# PSFB_transformer.net
KiCad netlist of a schematic drawn in Altium Designer
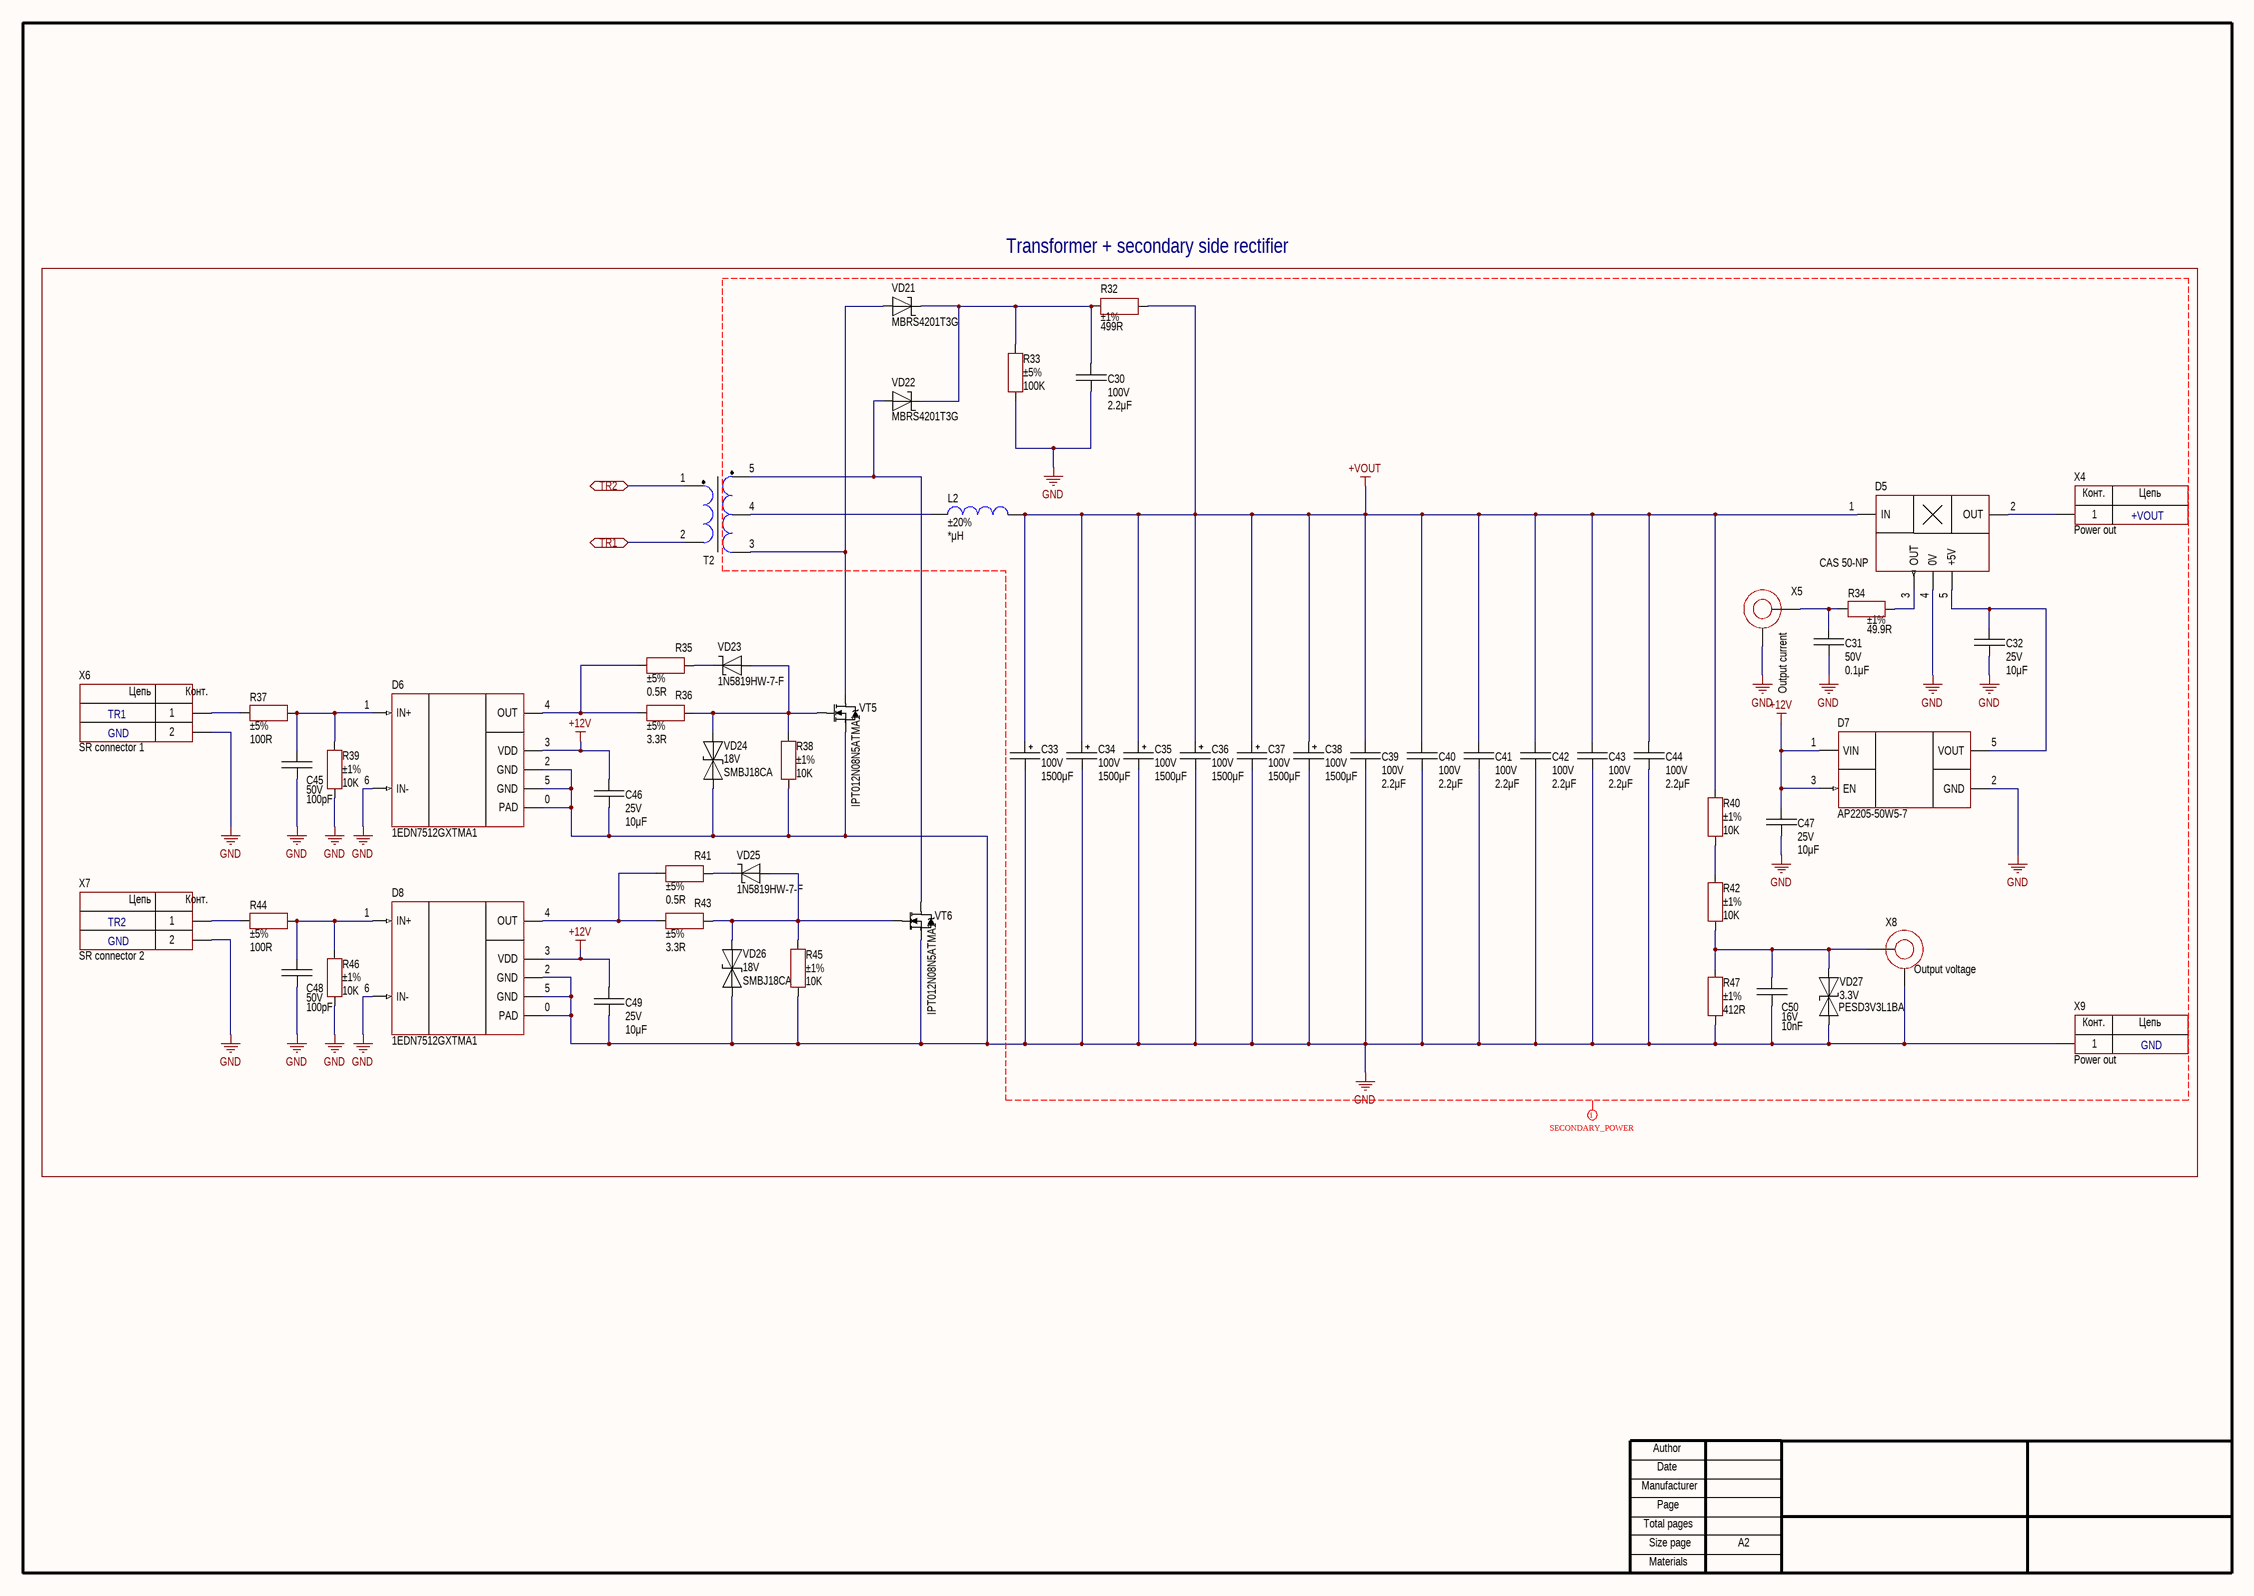
[diagram p0: PSFB_transformer.SchDoc]

(export (version "E")
  (design (tool "Eeschema 10.0.6"))
  (components
    (comp (ref "C30")
      (value "2.2μF")
      (footprint "CAP: 1206")
      (description "2.2µF ±10% 100V Ceramic Capacitor X7R 1206 (3216 Metric)")
      (fields
        (field (name "MANUFACTURER") "Yageo")
        (field (name "PARTNUMBER") "CC1206KKX7R0BB225")
        (field (name "VOLTAGE") "100V")
      )
      (libsource (lib "capacitor") (part "Ceramic_1206"))
    )
    (comp (ref "C31")
      (value "0.1μF")
      (footprint "CAP: 0805")
      (description "0.1µF ±10% 50V Ceramic Capacitor X7R 0805 (2012 Metric)")
      (fields
        (field (name "MANUFACTURER") "Yageo")
        (field (name "PARTNUMBER") "CC0805KRX7R9BB104")
        (field (name "VOLTAGE") "50V")
      )
      (libsource (lib "capacitor") (part "Ceramic_0805"))
    )
    (comp (ref "C32")
      (value "10μF")
      (footprint "CAP: 1206")
      (description "10µF ±10% 25V Ceramic Capacitor X7R 1206 (3216 Metric)")
      (fields
        (field (name "MANUFACTURER") "Yageo")
        (field (name "PARTNUMBER") "CC1206KKX7R8BB106")
        (field (name "VOLTAGE") "25V")
      )
      (libsource (lib "capacitor") (part "Ceramic_1206"))
    )
    (comp (ref "C33")
      (value "1500μF")
      (footprint "CAP: D30C10H37")
      (description "1500µF 100V Aluminum Electrolytic Capacitors Radial, Can - Snap-In  5000 Hrs @ 105°C")
      (fields
        (field (name "MANUFACTURER") "Nichicon")
        (field (name "PARTNUMBER") "LGY2A152MELB30")
        (field (name "VOLTAGE") "100V")
      )
      (libsource (lib "capacitor") (part "Aluminium"))
    )
    (comp (ref "C34")
      (value "1500μF")
      (footprint "CAP: D30C10H37")
      (description "1500µF 100V Aluminum Electrolytic Capacitors Radial, Can - Snap-In  5000 Hrs @ 105°C")
      (fields
        (field (name "MANUFACTURER") "Nichicon")
        (field (name "PARTNUMBER") "LGY2A152MELB30")
        (field (name "VOLTAGE") "100V")
      )
      (libsource (lib "capacitor") (part "Aluminium"))
    )
    (comp (ref "C35")
      (value "1500μF")
      (footprint "CAP: D30C10H37")
      (description "1500µF 100V Aluminum Electrolytic Capacitors Radial, Can - Snap-In  5000 Hrs @ 105°C")
      (fields
        (field (name "MANUFACTURER") "Nichicon")
        (field (name "PARTNUMBER") "LGY2A152MELB30")
        (field (name "VOLTAGE") "100V")
      )
      (libsource (lib "capacitor") (part "Aluminium"))
    )
    (comp (ref "C36")
      (value "1500μF")
      (footprint "CAP: D30C10H37")
      (description "1500µF 100V Aluminum Electrolytic Capacitors Radial, Can - Snap-In  5000 Hrs @ 105°C")
      (fields
        (field (name "MANUFACTURER") "Nichicon")
        (field (name "PARTNUMBER") "LGY2A152MELB30")
        (field (name "VOLTAGE") "100V")
      )
      (libsource (lib "capacitor") (part "Aluminium"))
    )
    (comp (ref "C37")
      (value "1500μF")
      (footprint "CAP: D30C10H37")
      (description "1500µF 100V Aluminum Electrolytic Capacitors Radial, Can - Snap-In  5000 Hrs @ 105°C")
      (fields
        (field (name "MANUFACTURER") "Nichicon")
        (field (name "PARTNUMBER") "LGY2A152MELB30")
        (field (name "VOLTAGE") "100V")
      )
      (libsource (lib "capacitor") (part "Aluminium"))
    )
    (comp (ref "C38")
      (value "1500μF")
      (footprint "CAP: D30C10H37")
      (description "1500µF 100V Aluminum Electrolytic Capacitors Radial, Can - Snap-In  5000 Hrs @ 105°C")
      (fields
        (field (name "MANUFACTURER") "Nichicon")
        (field (name "PARTNUMBER") "LGY2A152MELB30")
        (field (name "VOLTAGE") "100V")
      )
      (libsource (lib "capacitor") (part "Aluminium"))
    )
    (comp (ref "C39")
      (value "2.2μF")
      (footprint "CAP: 1206")
      (description "2.2µF ±10% 100V Ceramic Capacitor X7R 1206 (3216 Metric)")
      (fields
        (field (name "MANUFACTURER") "Yageo")
        (field (name "PARTNUMBER") "CC1206KKX7R0BB225")
        (field (name "VOLTAGE") "100V")
      )
      (libsource (lib "capacitor") (part "Ceramic_1206"))
    )
    (comp (ref "C40")
      (value "2.2μF")
      (footprint "CAP: 1206")
      (description "2.2µF ±10% 100V Ceramic Capacitor X7R 1206 (3216 Metric)")
      (fields
        (field (name "MANUFACTURER") "Yageo")
        (field (name "PARTNUMBER") "CC1206KKX7R0BB225")
        (field (name "VOLTAGE") "100V")
      )
      (libsource (lib "capacitor") (part "Ceramic_1206"))
    )
    (comp (ref "C41")
      (value "2.2μF")
      (footprint "CAP: 1206")
      (description "2.2µF ±10% 100V Ceramic Capacitor X7R 1206 (3216 Metric)")
      (fields
        (field (name "MANUFACTURER") "Yageo")
        (field (name "PARTNUMBER") "CC1206KKX7R0BB225")
        (field (name "VOLTAGE") "100V")
      )
      (libsource (lib "capacitor") (part "Ceramic_1206"))
    )
    (comp (ref "C42")
      (value "2.2μF")
      (footprint "CAP: 1206")
      (description "2.2µF ±10% 100V Ceramic Capacitor X7R 1206 (3216 Metric)")
      (fields
        (field (name "MANUFACTURER") "Yageo")
        (field (name "PARTNUMBER") "CC1206KKX7R0BB225")
        (field (name "VOLTAGE") "100V")
      )
      (libsource (lib "capacitor") (part "Ceramic_1206"))
    )
    (comp (ref "C43")
      (value "2.2μF")
      (footprint "CAP: 1206")
      (description "2.2µF ±10% 100V Ceramic Capacitor X7R 1206 (3216 Metric)")
      (fields
        (field (name "MANUFACTURER") "Yageo")
        (field (name "PARTNUMBER") "CC1206KKX7R0BB225")
        (field (name "VOLTAGE") "100V")
      )
      (libsource (lib "capacitor") (part "Ceramic_1206"))
    )
    (comp (ref "C44")
      (value "2.2μF")
      (footprint "CAP: 1206")
      (description "2.2µF ±10% 100V Ceramic Capacitor X7R 1206 (3216 Metric)")
      (fields
        (field (name "MANUFACTURER") "Yageo")
        (field (name "PARTNUMBER") "CC1206KKX7R0BB225")
        (field (name "VOLTAGE") "100V")
      )
      (libsource (lib "capacitor") (part "Ceramic_1206"))
    )
    (comp (ref "C45")
      (value "100pF")
      (footprint "CAP: 0805")
      (description "100pF ±5% 50V Ceramic Capacitor C0G, NP0 0805 (2012 Metric)")
      (fields
        (field (name "MANUFACTURER") "Yageo")
        (field (name "PARTNUMBER") "CC0805JRNPO9BN101")
        (field (name "VOLTAGE") "50V")
      )
      (libsource (lib "capacitor") (part "Ceramic_0805"))
    )
    (comp (ref "C46")
      (value "10μF")
      (footprint "CAP: 1206")
      (description "10µF ±10% 25V Ceramic Capacitor X7R 1206 (3216 Metric)")
      (fields
        (field (name "MANUFACTURER") "Yageo")
        (field (name "PARTNUMBER") "CC1206KKX7R8BB106")
        (field (name "VOLTAGE") "25V")
      )
      (libsource (lib "capacitor") (part "Ceramic_1206"))
    )
    (comp (ref "C47")
      (value "10μF")
      (footprint "CAP: 1206")
      (description "10µF ±10% 25V Ceramic Capacitor X7R 1206 (3216 Metric)")
      (fields
        (field (name "MANUFACTURER") "Yageo")
        (field (name "PARTNUMBER") "CC1206KKX7R8BB106")
        (field (name "VOLTAGE") "25V")
      )
      (libsource (lib "capacitor") (part "Ceramic_1206"))
    )
    (comp (ref "C48")
      (value "100pF")
      (footprint "CAP: 0805")
      (description "100pF ±5% 50V Ceramic Capacitor C0G, NP0 0805 (2012 Metric)")
      (fields
        (field (name "MANUFACTURER") "Yageo")
        (field (name "PARTNUMBER") "CC0805JRNPO9BN101")
        (field (name "VOLTAGE") "50V")
      )
      (libsource (lib "capacitor") (part "Ceramic_0805"))
    )
    (comp (ref "C49")
      (value "10μF")
      (footprint "CAP: 1206")
      (description "10µF ±10% 25V Ceramic Capacitor X7R 1206 (3216 Metric)")
      (fields
        (field (name "MANUFACTURER") "Yageo")
        (field (name "PARTNUMBER") "CC1206KKX7R8BB106")
        (field (name "VOLTAGE") "25V")
      )
      (libsource (lib "capacitor") (part "Ceramic_1206"))
    )
    (comp (ref "C50")
      (value "10nF")
      (footprint "CAP: 0805")
      (description "27pF ±5% 50V Ceramic Capacitor C0G, NP0 0805 (2012 Metric)")
      (fields
        (field (name "MANUFACTURER") "Yageo")
        (field (name "PARTNUMBER") "CC0805JKNPO7BN103")
        (field (name "VOLTAGE") "16V")
      )
      (libsource (lib "capacitor") (part "Ceramic_0805"))
    )
    (comp (ref "D5")
      (value "~")
      (footprint "SENSOR: LTS 25-NP")
      (description "Current Sensor 50A 1 Channel Flux Gate, Closed Loop Bidirectional Module")
      (fields
        (field (name "MANUFACTURER") "LEM")
        (field (name "VALUEMANUFACTURERPARTNUMBER") "IC current sensors, 50A, ±0.2%, 400 kHz, 12.5mV/A, -40...+85°C")
        (field (name "PARTNUMBER") "CAS 50-NP")
      )
      (libsource (lib "ic-sensor") (part "LTS 25-NP"))
    )
    (comp (ref "D6")
      (value "~")
      (footprint "6-WDFN")
      (description "Low-Side Gate Driver IC Inverting, Non-Inverting PG-WSON-6-1")
      (fields
        (field (name "MANUFACTURER") "Infineon")
        (field (name "VALUEMANUFACTURERPARTNUMBER") "Low gate driver, Non-Inverting, complementary, +4/-8A, 6.5/4.5ns, 4.5...20V, -55...+150°C, 6-WDFN")
        (field (name "PARTNUMBER") "1EDN7512GXTMA1")
      )
      (libsource (lib "MyLib") (part "1EDN7512BXTSA1"))
    )
    (comp (ref "D7")
      (value "~")
      (footprint "SOT23-5")
      (description "Linear Voltage Regulator IC Positive Fixed 1 Output  250mA SOT-25")
      (fields
        (field (name "MANUFACTURER") "Diodes Incorporated")
        (field (name "VALUEMANUFACTURERPARTNUMBER") "Linear voltage regulator, input 4...24V, 0.5V, output 5.0V, 0.25A, -40...+85°C, SOT23-6")
        (field (name "PARTNUMBER") "AP2205-50W5-7")
      )
      (libsource (lib "ic-power-supply") (part "AP2204K-3.3TRG1"))
    )
    (comp (ref "D8")
      (value "~")
      (footprint "6-WDFN")
      (description "Low-Side Gate Driver IC Inverting, Non-Inverting PG-WSON-6-1")
      (fields
        (field (name "MANUFACTURER") "Infineon")
        (field (name "VALUEMANUFACTURERPARTNUMBER") "Low gate driver, Non-Inverting, complementary, +4/-8A, 6.5/4.5ns, 4.5...20V, -55...+150°C, 6-WDFN")
        (field (name "PARTNUMBER") "1EDN7512GXTMA1")
      )
      (libsource (lib "MyLib") (part "1EDN7512BXTSA1"))
    )
    (comp (ref "L2")
      (value "*μH")
      (footprint "IND: R46.7/24.1/18 (H)")
      (description "Custom inductor, DNP")
      (fields
        (field (name "MANUFACTURER") "Magnetics")
        (field (name "PARTNUMBER") "0077438A7")
        (field (name "TOLERANCE") "±20%")
      )
      (libsource (lib "inductor") (part "Inductor_R46.7/24.1/18"))
    )
    (comp (ref "R32")
      (value "499R")
      (footprint "RES: 2512")
      (description "499 Ohms ±1% 1W Chip Resistor 2512 (6432 Metric) Moisture Resistant Thick Film")
      (fields
        (field (name "MANUFACTURER") "Yageo")
        (field (name "PARTNUMBER") "RC2512FK-07499RL")
        (field (name "TOLERANCE") "±1%")
      )
      (libsource (lib "resistor") (part "Resistor_2512"))
    )
    (comp (ref "R33")
      (value "100K")
      (footprint "RES: 1206")
      (description "100 kOhms ±5% 0.25W, 1/4W Chip Resistor 1206 (3216 Metric) Moisture Resistant Thick Film")
      (fields
        (field (name "MANUFACTURER") "Yageo")
        (field (name "PARTNUMBER") "RC1206JR-07100KL")
        (field (name "TOLERANCE") "±5%")
      )
      (libsource (lib "") (part "Resistor_1206_1"))
    )
    (comp (ref "R34")
      (value "49.9R")
      (footprint "RES: 0805")
      (description "49.9 Ohms ±1% 0.125W, 1/8W Chip Resistor 0805 (2012 Metric) Moisture Resistant Thick Film")
      (fields
        (field (name "MANUFACTURER") "Yageo")
        (field (name "PARTNUMBER") "RC0805FR-0749R9L")
        (field (name "TOLERANCE") "±1%")
      )
      (libsource (lib "") (part "Resistor_0805_1"))
    )
    (comp (ref "R35")
      (value "0.5R")
      (footprint "RES: 1206")
      (fields
        (field (name "MANUFACTURER") "Yageo")
        (field (name "PARTNUMBER") "RL1206JR-070R5L")
        (field (name "VALUEMANUFACTURERPARTNUMBER") "Resistor film, 0.5R, ±5%, 1206, 0.25W, -55...+125°C")
        (field (name "TOLERANCE") "±5%")
      )
      (libsource (lib "resistor") (part "Resistor_1206"))
    )
    (comp (ref "R36")
      (value "3.3R")
      (footprint "RES: 1206")
      (description "3.3 Ohms ±5% 0.25W, 1/4W Chip Resistor 1206 (3216 Metric) Moisture Resistant Thick Film")
      (fields
        (field (name "MANUFACTURER") "Yageo")
        (field (name "PARTNUMBER") "RC1206JR-073R3L")
        (field (name "TOLERANCE") "±5%")
      )
      (libsource (lib "resistor") (part "Resistor_1206"))
    )
    (comp (ref "R37")
      (value "100R")
      (footprint "RES: 0805")
      (description "100 Ohms ±5% 0.125W, 1/8W Chip Resistor 0805 (2012 Metric) Moisture Resistant Thick Film")
      (fields
        (field (name "MANUFACTURER") "Yageo")
        (field (name "PARTNUMBER") "RC0805JR-07100RL")
        (field (name "TOLERANCE") "±5%")
      )
      (libsource (lib "resistor") (part "Resistor_0805"))
    )
    (comp (ref "R38")
      (value "10K")
      (footprint "RES: 0805")
      (description "10 kOhms ±1% 0.125W, 1/8W Chip Resistor 0805 (2012 Metric) Moisture Resistant Thick Film")
      (fields
        (field (name "MANUFACTURER") "Yageo")
        (field (name "PARTNUMBER") "RC0805FR-0710KL")
        (field (name "TOLERANCE") "±1%")
      )
      (libsource (lib "resistor") (part "Resistor_0805"))
    )
    (comp (ref "R39")
      (value "10K")
      (footprint "RES: 0805")
      (description "10 kOhms ±1% 0.125W, 1/8W Chip Resistor 0805 (2012 Metric) Moisture Resistant Thick Film")
      (fields
        (field (name "MANUFACTURER") "Yageo")
        (field (name "PARTNUMBER") "RC0805FR-0710KL")
        (field (name "TOLERANCE") "±1%")
      )
      (libsource (lib "resistor") (part "Resistor_0805"))
    )
    (comp (ref "R40")
      (value "10K")
      (footprint "RES: 0805")
      (description "10 kOhms ±1% 0.125W, 1/8W Chip Resistor 0805 (2012 Metric) Moisture Resistant Thick Film")
      (fields
        (field (name "MANUFACTURER") "Yageo")
        (field (name "PARTNUMBER") "RC0805FR-0710KL")
        (field (name "TOLERANCE") "±1%")
      )
      (libsource (lib "resistor") (part "Resistor_0805"))
    )
    (comp (ref "R41")
      (value "0.5R")
      (footprint "RES: 1206")
      (fields
        (field (name "MANUFACTURER") "Yageo")
        (field (name "PARTNUMBER") "RL1206JR-070R5L")
        (field (name "VALUEMANUFACTURERPARTNUMBER") "Resistor film, 0.5R, ±5%, 1206, 0.25W, -55...+125°C")
        (field (name "TOLERANCE") "±5%")
      )
      (libsource (lib "resistor") (part "Resistor_1206"))
    )
    (comp (ref "R42")
      (value "10K")
      (footprint "RES: 0805")
      (description "10 kOhms ±1% 0.125W, 1/8W Chip Resistor 0805 (2012 Metric) Moisture Resistant Thick Film")
      (fields
        (field (name "MANUFACTURER") "Yageo")
        (field (name "PARTNUMBER") "RC0805FR-0710KL")
        (field (name "TOLERANCE") "±1%")
      )
      (libsource (lib "resistor") (part "Resistor_0805"))
    )
    (comp (ref "R43")
      (value "3.3R")
      (footprint "RES: 1206")
      (description "3.3 Ohms ±5% 0.25W, 1/4W Chip Resistor 1206 (3216 Metric) Moisture Resistant Thick Film")
      (fields
        (field (name "MANUFACTURER") "Yageo")
        (field (name "PARTNUMBER") "RC1206JR-073R3L")
        (field (name "TOLERANCE") "±5%")
      )
      (libsource (lib "resistor") (part "Resistor_1206"))
    )
    (comp (ref "R44")
      (value "100R")
      (footprint "RES: 0805")
      (description "100 Ohms ±5% 0.125W, 1/8W Chip Resistor 0805 (2012 Metric) Moisture Resistant Thick Film")
      (fields
        (field (name "MANUFACTURER") "Yageo")
        (field (name "PARTNUMBER") "RC0805JR-07100RL")
        (field (name "TOLERANCE") "±5%")
      )
      (libsource (lib "resistor") (part "Resistor_0805"))
    )
    (comp (ref "R45")
      (value "10K")
      (footprint "RES: 0805")
      (description "10 kOhms ±1% 0.125W, 1/8W Chip Resistor 0805 (2012 Metric) Moisture Resistant Thick Film")
      (fields
        (field (name "MANUFACTURER") "Yageo")
        (field (name "PARTNUMBER") "RC0805FR-0710KL")
        (field (name "TOLERANCE") "±1%")
      )
      (libsource (lib "resistor") (part "Resistor_0805"))
    )
    (comp (ref "R46")
      (value "10K")
      (footprint "RES: 0805")
      (description "10 kOhms ±1% 0.125W, 1/8W Chip Resistor 0805 (2012 Metric) Moisture Resistant Thick Film")
      (fields
        (field (name "MANUFACTURER") "Yageo")
        (field (name "PARTNUMBER") "RC0805FR-0710KL")
        (field (name "TOLERANCE") "±1%")
      )
      (libsource (lib "resistor") (part "Resistor_0805"))
    )
    (comp (ref "R47")
      (value "412R")
      (footprint "RES: 0805")
      (description "412 Ohms ±1% 0.125W, 1/8W Chip Resistor 0805 (2012 Metric) Moisture Resistant Thick Film")
      (fields
        (field (name "MANUFACTURER") "Yageo")
        (field (name "PARTNUMBER") "RC0805FR-07412RL")
        (field (name "TOLERANCE") "±1%")
      )
      (libsource (lib "resistor") (part "Resistor_0805"))
    )
    (comp (ref "T2")
      (value "~")
      (footprint "TRANS: ETD59/31/22_FB")
      (description "N97 B66397G0000X197 сore / B66398W1024T001 coil former")
      (fields
        (field (name "MANUFACTURER") "Epcos")
        (field (name "VALUEMANUFACTURERPARTNUMBER") "Transformer, ")
      )
      (libsource (lib "transformer") (part "ETD59/31/22_FB"))
    )
    (comp (ref "VD21")
      (value "~")
      (footprint "DIODE: SMC")
      (description "Diode Schottky 200V 4A Surface Mount SMC")
      (fields
        (field (name "MANUFACTURER") "Diodes Incorporated")
        (field (name "VALUEMANUFACTURERPARTNUMBER") "Schottky diode, 200V, 1A, 0.45V, 20pF, SMC, -55...+150°C")
        (field (name "PARTNUMBER") "MBRS4201T3G")
      )
      (libsource (lib "diode") (part "Schottky_single"))
    )
    (comp (ref "VD22")
      (value "~")
      (footprint "DIODE: SMC")
      (description "Diode Schottky 200V 4A Surface Mount SMC")
      (fields
        (field (name "MANUFACTURER") "Diodes Incorporated")
        (field (name "VALUEMANUFACTURERPARTNUMBER") "Schottky diode, 200V, 1A, 0.45V, 20pF, SMC, -55...+150°C")
        (field (name "PARTNUMBER") "MBRS4201T3G")
      )
      (libsource (lib "diode") (part "Schottky_single"))
    )
    (comp (ref "VD23")
      (value "~")
      (footprint "DIODE: SOD123")
      (description "Diode Schottky 40V 1A Surface Mount SOD-123C")
      (fields
        (field (name "MANUFACTURER") "Diodes Incorporated")
        (field (name "VALUEMANUFACTURERPARTNUMBER") "Schottky diode, 40V, 1A, 0.45V, 15pF, SOD-123, -55...+150°C")
        (field (name "PARTNUMBER") "1N5819HW-7-F")
      )
      (libsource (lib "diode") (part "Schottky_single"))
    )
    (comp (ref "VD24")
      (value "~")
      (footprint "DIODE: SMB")
      (description "29.2V Clamp 20.6A Ipp Tvs Diode Surface Mount DO-214AA (SMBJ)")
      (fields
        (field (name "MANUFACTURER") "Diodes Incorporated")
        (field (name "VALUEMANUFACTURERPARTNUMBER") "TVS diode, 18V, 600W, , , SMB, -55...+150°C")
        (field (name "VOLTAGE") "18V")
        (field (name "PARTNUMBER") "SMBJ18CA")
      )
      (libsource (lib "diode") (part "TVS_single"))
    )
    (comp (ref "VD25")
      (value "~")
      (footprint "DIODE: SOD123")
      (description "Diode Schottky 40V 1A Surface Mount SOD-123C")
      (fields
        (field (name "MANUFACTURER") "Diodes Incorporated")
        (field (name "VALUEMANUFACTURERPARTNUMBER") "Schottky diode, 40V, 1A, 0.45V, 15pF, SOD-123, -55...+150°C")
        (field (name "PARTNUMBER") "1N5819HW-7-F")
      )
      (libsource (lib "diode") (part "Schottky_single"))
    )
    (comp (ref "VD26")
      (value "~")
      (footprint "DIODE: SMB")
      (description "29.2V Clamp 20.6A Ipp Tvs Diode Surface Mount DO-214AA (SMBJ)")
      (fields
        (field (name "MANUFACTURER") "Diodes Incorporated")
        (field (name "VALUEMANUFACTURERPARTNUMBER") "TVS diode, 18V, 600W, , , SMB, -55...+150°C")
        (field (name "VOLTAGE") "18V")
        (field (name "PARTNUMBER") "SMBJ18CA")
      )
      (libsource (lib "diode") (part "TVS_single"))
    )
    (comp (ref "VD27")
      (value "~")
      (footprint "DIODE: SOD323")
      (description "3.3V Reverse Standoff 26V Clamp 18A (8/20µs) Ipp Tvs Diode Surface Mount SOD-323")
      (fields
        (field (name "MANUFACTURER") "Diodes Incorporated")
        (field (name "VALUEMANUFACTURERPARTNUMBER") "TVS diode, 3.3V, 500W, , , SOD-323, -55...+150°C")
        (field (name "VOLTAGE") "3.3V")
        (field (name "PARTNUMBER") "PESD3V3L1BA")
      )
      (libsource (lib "diode") (part "TVS_single"))
    )
    (comp (ref "VT5")
      (value "~")
      (footprint "8-TDSON")
      (description "N-Channel 80V 300A (Tc) 375W (Tc) Surface Mount PG-HSOF-8-1")
      (fields
        (field (name "MANUFACTURER") "Infineon Technologies")
        (field (name "VALUEMANUFACTURERPARTNUMBER") "MOSFET N-channel transistor, 100V, 300A, 223nC, 375W, 1.2mOhm, 17000pF, 8-TDSON, -55...+150°C")
        (field (name "PARTNUMBER") "IPT012N08N5ATMA1")
      )
      (libsource (lib "transistor") (part "MOSFET_N_123"))
    )
    (comp (ref "VT6")
      (value "~")
      (footprint "8-TDSON")
      (description "N-Channel 80V 300A (Tc) 375W (Tc) Surface Mount PG-HSOF-8-1")
      (fields
        (field (name "MANUFACTURER") "Infineon Technologies")
        (field (name "VALUEMANUFACTURERPARTNUMBER") "MOSFET N-channel transistor, 100V, 300A, 223nC, 375W, 1.2mOhm, 17000pF, 8-TDSON, -55...+150°C")
        (field (name "PARTNUMBER") "IPT012N08N5ATMA1")
      )
      (libsource (lib "transistor") (part "MOSFET_N_123"))
    )
    (comp (ref "X4")
      (value "~")
      (footprint "7461098_for HAL")
      (description "25 Pin Shank Terminal M6 Through Hole")
      (fields
        (field (name "MANUFACTURER") "Würth Elektronik")
        (field (name "VALUEMANUFACTURERPARTNUMBER") "Power connector, , 250A")
        (field (name "COMMENTTEXT") "Power out")
      )
      (libsource (lib "connector") (part "Connector_single_power"))
    )
    (comp (ref "X5")
      (value "~")
      (footprint "60311002111526")
      (description "SMA Connector Jack, Female Socket 50Ohm Through Hole Solder")
      (fields
        (field (name "MANUFACTURER") "Würth Elektronik")
        (field (name "VALUEMANUFACTURERPARTNUMBER") "Connector SMA, 50 Ohm, 6Hz")
        (field (name "COMMENTTEXT") "Output current")
      )
      (libsource (lib "connector") (part "Connector_SMA"))
    )
    (comp (ref "X6")
      (value "~")
      (footprint "SM02B-SRSS-TB(LF)(SN)")
      (description "Connector Header Surface Mount, Right Angle 2 position 0.039\" (1.00mm)")
      (fields
        (field (name "MANUFACTURER") "JST")
        (field (name "VALUEMANUFACTURERPARTNUMBER") "Connector, 2pin, 1.00mm, 50V, 25A")
        (field (name "COMMENTTEXT") "SR connector 1")
      )
      (libsource (lib "MyLib") (part "Connector_SM02B-SRSS"))
    )
    (comp (ref "X7")
      (value "~")
      (footprint "SM02B-SRSS-TB(LF)(SN)")
      (description "Connector Header Surface Mount, Right Angle 2 position 0.039\" (1.00mm)")
      (fields
        (field (name "MANUFACTURER") "JST")
        (field (name "VALUEMANUFACTURERPARTNUMBER") "Connector, 2pin, 1.00mm, 50V, 25A")
        (field (name "COMMENTTEXT") "SR connector 2")
      )
      (libsource (lib "MyLib") (part "Connector_SM02B-SRSS"))
    )
    (comp (ref "X8")
      (value "~")
      (footprint "60311002111526")
      (description "SMA Connector Jack, Female Socket 50Ohm Through Hole Solder")
      (fields
        (field (name "MANUFACTURER") "Würth Elektronik")
        (field (name "VALUEMANUFACTURERPARTNUMBER") "Connector SMA, 50 Ohm, 6Hz")
        (field (name "COMMENTTEXT") "Output voltage")
      )
      (libsource (lib "connector") (part "Connector_SMA"))
    )
    (comp (ref "X9")
      (value "~")
      (footprint "7461098_for HAL")
      (description "25 Pin Shank Terminal M6 Through Hole")
      (fields
        (field (name "MANUFACTURER") "Würth Elektronik")
        (field (name "VALUEMANUFACTURERPARTNUMBER") "Power connector, , 250A")
        (field (name "COMMENTTEXT") "Power out")
      )
      (libsource (lib "connector") (part "Connector_single_power"))
    )
  )
  (nets
    (net (code "1") (name "+12V") (class "Default")
      (node (ref "C46") (pin "1") (pinfunction "1_1") (pintype "passive"))
      (node (ref "C47") (pin "1") (pinfunction "1_1") (pintype "passive"))
      (node (ref "C49") (pin "1") (pinfunction "1_1") (pintype "passive"))
      (node (ref "D6") (pin "3") (pinfunction "VDD_3") (pintype "passive"))
      (node (ref "D7") (pin "1") (pinfunction "VIN_1") (pintype "passive"))
      (node (ref "D7") (pin "3") (pinfunction "EN_3") (pintype "input"))
      (node (ref "D8") (pin "3") (pinfunction "VDD_3") (pintype "passive"))
    )
    (net (code "2") (name "+VOUT") (class "Default")
      (node (ref "C33") (pin "1") (pinfunction "1_1") (pintype "passive"))
      (node (ref "C34") (pin "1") (pinfunction "1_1") (pintype "passive"))
      (node (ref "C35") (pin "1") (pinfunction "1_1") (pintype "passive"))
      (node (ref "C36") (pin "1") (pinfunction "1_1") (pintype "passive"))
      (node (ref "C37") (pin "1") (pinfunction "1_1") (pintype "passive"))
      (node (ref "C38") (pin "1") (pinfunction "1_1") (pintype "passive"))
      (node (ref "C39") (pin "1") (pinfunction "1_1") (pintype "passive"))
      (node (ref "C40") (pin "1") (pinfunction "1_1") (pintype "passive"))
      (node (ref "C41") (pin "1") (pinfunction "1_1") (pintype "passive"))
      (node (ref "C42") (pin "1") (pinfunction "1_1") (pintype "passive"))
      (node (ref "C43") (pin "1") (pinfunction "1_1") (pintype "passive"))
      (node (ref "C44") (pin "1") (pinfunction "1_1") (pintype "passive"))
      (node (ref "D5") (pin "1") (pinfunction "IN_1") (pintype "passive"))
      (node (ref "L2") (pin "1") (pinfunction "1_1") (pintype "passive"))
      (node (ref "R32") (pin "2") (pinfunction "2_2") (pintype "passive"))
      (node (ref "R40") (pin "2") (pinfunction "2_2") (pintype "passive"))
    )
    (net (code "3") (name "/TR1") (class "Default")
      (node (ref "T2") (pin "2") (pinfunction "2_2") (pintype "power_in"))
    )
    (net (code "4") (name "/TR2") (class "Default")
      (node (ref "T2") (pin "1") (pinfunction "1_1") (pintype "power_in"))
    )
    (net (code "5") (name "GND") (class "Default")
      (node (ref "C30") (pin "2") (pinfunction "2_2") (pintype "passive"))
      (node (ref "C31") (pin "1") (pinfunction "1_1") (pintype "passive"))
      (node (ref "C32") (pin "2") (pinfunction "2_2") (pintype "passive"))
      (node (ref "C33") (pin "2") (pinfunction "2_2") (pintype "passive"))
      (node (ref "C34") (pin "2") (pinfunction "2_2") (pintype "passive"))
      (node (ref "C35") (pin "2") (pinfunction "2_2") (pintype "passive"))
      (node (ref "C36") (pin "2") (pinfunction "2_2") (pintype "passive"))
      (node (ref "C37") (pin "2") (pinfunction "2_2") (pintype "passive"))
      (node (ref "C38") (pin "2") (pinfunction "2_2") (pintype "passive"))
      (node (ref "C39") (pin "2") (pinfunction "2_2") (pintype "passive"))
      (node (ref "C40") (pin "2") (pinfunction "2_2") (pintype "passive"))
      (node (ref "C41") (pin "2") (pinfunction "2_2") (pintype "passive"))
      (node (ref "C42") (pin "2") (pinfunction "2_2") (pintype "passive"))
      (node (ref "C43") (pin "2") (pinfunction "2_2") (pintype "passive"))
      (node (ref "C44") (pin "2") (pinfunction "2_2") (pintype "passive"))
      (node (ref "C45") (pin "1") (pinfunction "1_1") (pintype "passive"))
      (node (ref "C46") (pin "2") (pinfunction "2_2") (pintype "passive"))
      (node (ref "C47") (pin "2") (pinfunction "2_2") (pintype "passive"))
      (node (ref "C48") (pin "1") (pinfunction "1_1") (pintype "passive"))
      (node (ref "C49") (pin "2") (pinfunction "2_2") (pintype "passive"))
      (node (ref "C50") (pin "1") (pinfunction "1_1") (pintype "passive"))
      (node (ref "D5") (pin "4") (pinfunction "0V_4") (pintype "passive"))
      (node (ref "D6") (pin "0") (pinfunction "PAD_0") (pintype "passive"))
      (node (ref "D6") (pin "2") (pinfunction "GND_2") (pintype "passive"))
      (node (ref "D6") (pin "5") (pinfunction "GND_5") (pintype "passive"))
      (node (ref "D6") (pin "6") (pinfunction "IN-_6") (pintype "input"))
      (node (ref "D7") (pin "2") (pinfunction "GND_2") (pintype "passive"))
      (node (ref "D8") (pin "0") (pinfunction "PAD_0") (pintype "passive"))
      (node (ref "D8") (pin "2") (pinfunction "GND_2") (pintype "passive"))
      (node (ref "D8") (pin "5") (pinfunction "GND_5") (pintype "passive"))
      (node (ref "D8") (pin "6") (pinfunction "IN-_6") (pintype "input"))
      (node (ref "R33") (pin "1") (pinfunction "1_1") (pintype "passive"))
      (node (ref "R38") (pin "1") (pinfunction "1_1") (pintype "passive"))
      (node (ref "R39") (pin "1") (pinfunction "1_1") (pintype "passive"))
      (node (ref "R45") (pin "1") (pinfunction "1_1") (pintype "passive"))
      (node (ref "R46") (pin "1") (pinfunction "1_1") (pintype "passive"))
      (node (ref "R47") (pin "1") (pinfunction "1_1") (pintype "passive"))
      (node (ref "VD24") (pin "2") (pinfunction "C_2") (pintype "passive"))
      (node (ref "VD26") (pin "2") (pinfunction "C_2") (pintype "passive"))
      (node (ref "VD27") (pin "1") (pinfunction "A_1") (pintype "passive"))
      (node (ref "VT5") (pin "3") (pinfunction "S_3") (pintype "passive"))
      (node (ref "VT6") (pin "3") (pinfunction "S_3") (pintype "passive"))
      (node (ref "X5") (pin "2") (pinfunction "2_2") (pintype "passive"))
      (node (ref "X6") (pin "2") (pinfunction "2_2") (pintype "passive"))
      (node (ref "X7") (pin "2") (pinfunction "2_2") (pintype "passive"))
      (node (ref "X8") (pin "2") (pinfunction "2_2") (pintype "passive"))
      (node (ref "X9") (pin "1") (pinfunction "1_1") (pintype "passive"))
    )
    (net (code "6") (name "Net-(C30-Pad1)") (class "Default")
      (node (ref "C30") (pin "1") (pinfunction "1_1") (pintype "passive"))
      (node (ref "R32") (pin "1") (pinfunction "1_1") (pintype "passive"))
      (node (ref "R33") (pin "2") (pinfunction "2_2") (pintype "passive"))
      (node (ref "VD21") (pin "2") (pinfunction "2_2") (pintype "passive"))
      (node (ref "VD22") (pin "2") (pinfunction "2_2") (pintype "passive"))
    )
    (net (code "7") (name "Net-(C31-Pad2)") (class "Default")
      (node (ref "C31") (pin "2") (pinfunction "2_2") (pintype "passive"))
      (node (ref "R34") (pin "2") (pinfunction "2_2") (pintype "passive"))
      (node (ref "X5") (pin "1") (pinfunction "1_1") (pintype "passive"))
    )
    (net (code "8") (name "Net-(D5-+5V)") (class "Default")
      (node (ref "C32") (pin "1") (pinfunction "1_1") (pintype "passive"))
      (node (ref "D5") (pin "5") (pinfunction "+5V_5") (pintype "passive"))
      (node (ref "D7") (pin "5") (pinfunction "VOUT_5") (pintype "passive"))
    )
    (net (code "9") (name "Net-(D5-OUT-Pad2)") (class "Default")
      (node (ref "D5") (pin "2") (pinfunction "OUT_2") (pintype "passive"))
      (node (ref "X4") (pin "1") (pinfunction "1_1") (pintype "passive"))
    )
    (net (code "10") (name "Net-(D5-OUT-Pad3)") (class "Default")
      (node (ref "D5") (pin "3") (pinfunction "OUT_3") (pintype "output"))
      (node (ref "R34") (pin "1") (pinfunction "1_1") (pintype "passive"))
    )
    (net (code "11") (name "Net-(D6-IN+)") (class "Default")
      (node (ref "C45") (pin "2") (pinfunction "2_2") (pintype "passive"))
      (node (ref "D6") (pin "1") (pinfunction "IN+_1") (pintype "input"))
      (node (ref "R37") (pin "2") (pinfunction "2_2") (pintype "passive"))
      (node (ref "R39") (pin "2") (pinfunction "2_2") (pintype "passive"))
    )
    (net (code "12") (name "Net-(D6-OUT)") (class "Default")
      (node (ref "D6") (pin "4") (pinfunction "OUT_4") (pintype "passive"))
      (node (ref "R35") (pin "1") (pinfunction "1_1") (pintype "passive"))
      (node (ref "R36") (pin "1") (pinfunction "1_1") (pintype "passive"))
    )
    (net (code "13") (name "Net-(D8-IN+)") (class "Default")
      (node (ref "C48") (pin "2") (pinfunction "2_2") (pintype "passive"))
      (node (ref "D8") (pin "1") (pinfunction "IN+_1") (pintype "input"))
      (node (ref "R44") (pin "2") (pinfunction "2_2") (pintype "passive"))
      (node (ref "R46") (pin "2") (pinfunction "2_2") (pintype "passive"))
    )
    (net (code "14") (name "Net-(D8-OUT)") (class "Default")
      (node (ref "D8") (pin "4") (pinfunction "OUT_4") (pintype "passive"))
      (node (ref "R41") (pin "1") (pinfunction "1_1") (pintype "passive"))
      (node (ref "R43") (pin "1") (pinfunction "1_1") (pintype "passive"))
    )
    (net (code "15") (name "Net-(L2-Pad2)") (class "Default")
      (node (ref "L2") (pin "2") (pinfunction "2_2") (pintype "passive"))
      (node (ref "T2") (pin "4") (pinfunction "4_4") (pintype "power_in"))
    )
    (net (code "16") (name "Net-(R35-Pad2)") (class "Default")
      (node (ref "R35") (pin "2") (pinfunction "2_2") (pintype "passive"))
      (node (ref "VD23") (pin "2") (pinfunction "2_2") (pintype "passive"))
    )
    (net (code "17") (name "Net-(R37-Pad1)") (class "Default")
      (node (ref "R37") (pin "1") (pinfunction "1_1") (pintype "passive"))
      (node (ref "X6") (pin "1") (pinfunction "1_1") (pintype "passive"))
    )
    (net (code "18") (name "Net-(R40-Pad1)") (class "Default")
      (node (ref "R40") (pin "1") (pinfunction "1_1") (pintype "passive"))
      (node (ref "R42") (pin "2") (pinfunction "2_2") (pintype "passive"))
    )
    (net (code "19") (name "Net-(R41-Pad2)") (class "Default")
      (node (ref "R41") (pin "2") (pinfunction "2_2") (pintype "passive"))
      (node (ref "VD25") (pin "2") (pinfunction "2_2") (pintype "passive"))
    )
    (net (code "20") (name "Net-(R44-Pad1)") (class "Default")
      (node (ref "R44") (pin "1") (pinfunction "1_1") (pintype "passive"))
      (node (ref "X7") (pin "1") (pinfunction "1_1") (pintype "passive"))
    )
    (net (code "21") (name "Net-(VD24-A)") (class "Default")
      (node (ref "R36") (pin "2") (pinfunction "2_2") (pintype "passive"))
      (node (ref "R38") (pin "2") (pinfunction "2_2") (pintype "passive"))
      (node (ref "VD23") (pin "1") (pinfunction "1_1") (pintype "passive"))
      (node (ref "VD24") (pin "1") (pinfunction "A_1") (pintype "passive"))
      (node (ref "VT5") (pin "1") (pinfunction "G_1") (pintype "passive"))
    )
    (net (code "22") (name "Net-(VD26-A)") (class "Default")
      (node (ref "R43") (pin "2") (pinfunction "2_2") (pintype "passive"))
      (node (ref "R45") (pin "2") (pinfunction "2_2") (pintype "passive"))
      (node (ref "VD25") (pin "1") (pinfunction "1_1") (pintype "passive"))
      (node (ref "VD26") (pin "1") (pinfunction "A_1") (pintype "passive"))
      (node (ref "VT6") (pin "1") (pinfunction "G_1") (pintype "passive"))
    )
    (net (code "23") (name "Net-(VD27-C)") (class "Default")
      (node (ref "C50") (pin "2") (pinfunction "2_2") (pintype "passive"))
      (node (ref "R42") (pin "1") (pinfunction "1_1") (pintype "passive"))
      (node (ref "R47") (pin "2") (pinfunction "2_2") (pintype "passive"))
      (node (ref "VD27") (pin "2") (pinfunction "C_2") (pintype "passive"))
      (node (ref "X8") (pin "1") (pinfunction "1_1") (pintype "passive"))
    )
    (net (code "24") (name "Net-(VT5-D)") (class "Default")
      (node (ref "T2") (pin "3") (pinfunction "3_3") (pintype "power_in"))
      (node (ref "VD21") (pin "1") (pinfunction "1_1") (pintype "passive"))
      (node (ref "VT5") (pin "2") (pinfunction "D_2") (pintype "passive"))
    )
    (net (code "25") (name "Net-(VT6-D)") (class "Default")
      (node (ref "T2") (pin "5") (pinfunction "5_5") (pintype "power_in"))
      (node (ref "VD22") (pin "1") (pinfunction "1_1") (pintype "passive"))
      (node (ref "VT6") (pin "2") (pinfunction "D_2") (pintype "passive"))
    )
  )
)
